# PressureSensorShield.net
KiCad netlist of a schematic drawn in EAGLE
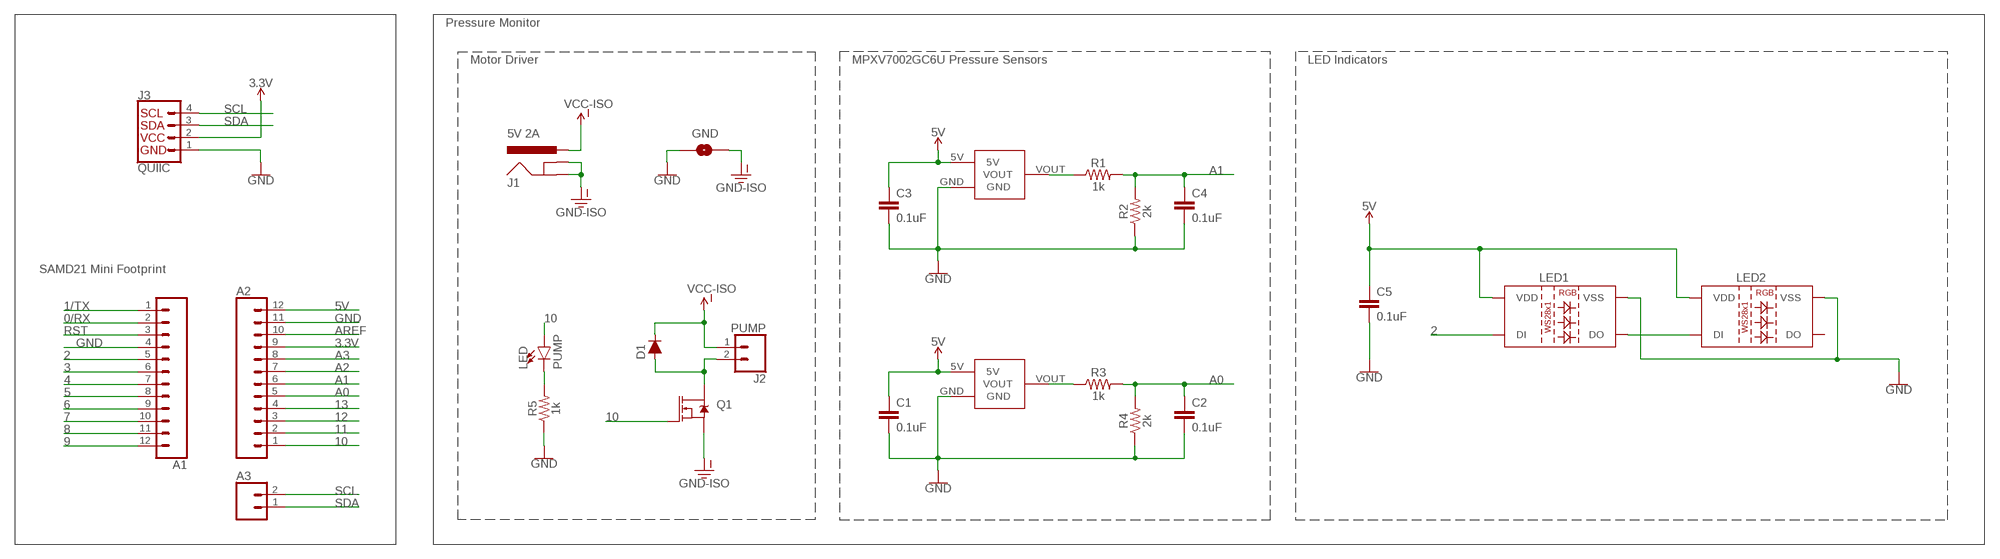
[diagram p0: schematic, sheet 1]

(export (version "E")
  (design (tool "Eeschema 10.0.6"))
  (components
    (comp (ref "A1")
      (value "CONN_12")
      (footprint "eagle-import:1X12")
      (libsource (lib "eagle-import") (part "CONN_12"))
    )
    (comp (ref "A2")
      (value "CONN_12")
      (footprint "eagle-import:1X12")
      (libsource (lib "eagle-import") (part "CONN_12"))
    )
    (comp (ref "A3")
      (value "CONN_02")
      (footprint "eagle-import:1X02")
      (libsource (lib "eagle-import") (part "CONN_02"))
    )
    (comp (ref "C1")
      (value "0.1uF")
      (footprint "eagle-import:CAP-PTH-SMALL-KIT")
      (libsource (lib "eagle-import") (part "0.1UF-KIT-EZ-50V-20%"))
    )
    (comp (ref "C2")
      (value "0.1uF")
      (footprint "eagle-import:CAP-PTH-SMALL-KIT")
      (libsource (lib "eagle-import") (part "0.1UF-KIT-EZ-50V-20%"))
    )
    (comp (ref "C3")
      (value "0.1uF")
      (footprint "eagle-import:CAP-PTH-SMALL-KIT")
      (libsource (lib "eagle-import") (part "0.1UF-KIT-EZ-50V-20%"))
    )
    (comp (ref "C4")
      (value "0.1uF")
      (footprint "eagle-import:CAP-PTH-SMALL-KIT")
      (libsource (lib "eagle-import") (part "0.1UF-KIT-EZ-50V-20%"))
    )
    (comp (ref "C5")
      (value "0.1uF")
      (footprint "eagle-import:CAP-PTH-SMALL-KIT")
      (libsource (lib "eagle-import") (part "0.1UF-KIT-EZ-50V-20%"))
    )
    (comp (ref "D1")
      (value "DIODE-KIT")
      (footprint "eagle-import:DIODE-1N4148-KIT")
      (libsource (lib "eagle-import") (part "DIODE-KIT"))
    )
    (comp (ref "GND")
      (value "JUMPER-SMT_2_NO_NO-SILK")
      (footprint "eagle-import:SMT-JUMPER_2_NO_NO-SILK")
      (libsource (lib "eagle-import") (part "JUMPER-SMT_2_NO_NO-SILK"))
    )
    (comp (ref "J1")
      (value "5V 2A")
      (footprint "eagle-import:POWER_JACK_PTH")
      (libsource (lib "eagle-import") (part "POWER_JACK"))
    )
    (comp (ref "J2")
      (value "PUMP")
      (footprint "eagle-import:SCREWTERMINAL-3.5MM-2")
      (libsource (lib "eagle-import") (part "CONN_023.5MM"))
    )
    (comp (ref "J3")
      (value "QUIIC")
      (footprint "eagle-import:JST04_1MM_RA")
      (libsource (lib "eagle-import") (part "I2C_STANDARDQWIIC"))
    )
    (comp (ref "LED")
      (value "PUMP")
      (footprint "eagle-import:LED_3MM")
      (libsource (lib "eagle-import") (part "LED3MM"))
    )
    (comp (ref "LED1")
      (value "WS2812B")
      (footprint "eagle-import:WS2812B")
      (libsource (lib "eagle-import") (part "WS2812B"))
    )
    (comp (ref "LED2")
      (value "WS2812B")
      (footprint "eagle-import:WS2812B")
      (libsource (lib "eagle-import") (part "WS2812B"))
    )
    (comp (ref "Q1")
      (value "MOSFET-NCH-FQP30N06L")
      (footprint "eagle-import:TO220V")
      (libsource (lib "eagle-import") (part "MOSFET-NCH-FQP30N06L"))
    )
    (comp (ref "R1")
      (value "1k")
      (footprint "eagle-import:AXIAL-0.3-KIT")
      (libsource (lib "eagle-import") (part "1KOHM-HORIZ_KIT-1/4W-1%"))
    )
    (comp (ref "R2")
      (value "2k")
      (footprint "eagle-import:AXIAL-0.3-KIT")
      (libsource (lib "eagle-import") (part "1KOHM-HORIZ_KIT-1/4W-1%"))
    )
    (comp (ref "R3")
      (value "1k")
      (footprint "eagle-import:AXIAL-0.3-KIT")
      (libsource (lib "eagle-import") (part "1KOHM-HORIZ_KIT-1/4W-1%"))
    )
    (comp (ref "R4")
      (value "2k")
      (footprint "eagle-import:AXIAL-0.3-KIT")
      (libsource (lib "eagle-import") (part "1KOHM-HORIZ_KIT-1/4W-1%"))
    )
    (comp (ref "R5")
      (value "1k")
      (footprint "eagle-import:AXIAL-0.3-KIT")
      (libsource (lib "eagle-import") (part "1KOHM-HORIZ_KIT-1/4W-1%"))
    )
    (comp (ref "SENSOR")
      (value "SENSOR 1")
      (footprint "eagle-import:SMALL_OUTLINE")
      (libsource (lib "eagle-import") (part "MPXV7002GC6T1"))
    )
    (comp (ref "SENSOR2")
      (value "SENSOR 2")
      (footprint "eagle-import:SMALL_OUTLINE")
      (libsource (lib "eagle-import") (part "MPXV7002GC6T1"))
    )
  )
  (nets
    (net (code "1") (name "/0{slash}RX") (class "Default")
      (node (ref "A1") (pin "2") (pinfunction "2_2") (pintype "passive"))
    )
    (net (code "2") (name "/1{slash}TX") (class "Default")
      (node (ref "A1") (pin "1") (pinfunction "1_1") (pintype "passive"))
    )
    (net (code "3") (name "/2") (class "Default")
      (node (ref "A1") (pin "5") (pinfunction "5_5") (pintype "passive"))
      (node (ref "LED1") (pin "4") (pinfunction "DI_4") (pintype "bidirectional"))
    )
    (net (code "4") (name "/3") (class "Default")
      (node (ref "A1") (pin "6") (pinfunction "6_6") (pintype "passive"))
    )
    (net (code "5") (name "/4") (class "Default")
      (node (ref "A1") (pin "7") (pinfunction "7_7") (pintype "passive"))
    )
    (net (code "6") (name "/5") (class "Default")
      (node (ref "A1") (pin "8") (pinfunction "8_8") (pintype "passive"))
    )
    (net (code "7") (name "/6") (class "Default")
      (node (ref "A1") (pin "9") (pinfunction "9_9") (pintype "passive"))
    )
    (net (code "8") (name "/7") (class "Default")
      (node (ref "A1") (pin "10") (pinfunction "10_10") (pintype "passive"))
    )
    (net (code "9") (name "/8") (class "Default")
      (node (ref "A1") (pin "11") (pinfunction "11_11") (pintype "passive"))
    )
    (net (code "10") (name "/9") (class "Default")
      (node (ref "A1") (pin "12") (pinfunction "12_12") (pintype "passive"))
    )
    (net (code "11") (name "/10") (class "Default")
      (node (ref "A2") (pin "1") (pinfunction "1_1") (pintype "passive"))
      (node (ref "LED") (pin "A") (pinfunction "A_A") (pintype "passive"))
      (node (ref "Q1") (pin "1") (pinfunction "G_1") (pintype "bidirectional"))
    )
    (net (code "12") (name "/11") (class "Default")
      (node (ref "A2") (pin "2") (pinfunction "2_2") (pintype "passive"))
    )
    (net (code "13") (name "/12") (class "Default")
      (node (ref "A2") (pin "3") (pinfunction "3_3") (pintype "passive"))
    )
    (net (code "14") (name "/13") (class "Default")
      (node (ref "A2") (pin "4") (pinfunction "4_4") (pintype "passive"))
    )
    (net (code "15") (name "/A0") (class "Default")
      (node (ref "A2") (pin "5") (pinfunction "5_5") (pintype "passive"))
      (node (ref "C2") (pin "1") (pinfunction "1_1") (pintype "passive"))
      (node (ref "R3") (pin "P$2") (pinfunction "2_P$2") (pintype "passive"))
      (node (ref "R4") (pin "P$2") (pinfunction "2_P$2") (pintype "passive"))
    )
    (net (code "16") (name "/A1") (class "Default")
      (node (ref "A2") (pin "6") (pinfunction "6_6") (pintype "passive"))
      (node (ref "C4") (pin "1") (pinfunction "1_1") (pintype "passive"))
      (node (ref "R1") (pin "P$2") (pinfunction "2_P$2") (pintype "passive"))
      (node (ref "R2") (pin "P$2") (pinfunction "2_P$2") (pintype "passive"))
    )
    (net (code "17") (name "/A2") (class "Default")
      (node (ref "A2") (pin "7") (pinfunction "7_7") (pintype "passive"))
    )
    (net (code "18") (name "/A3") (class "Default")
      (node (ref "A2") (pin "8") (pinfunction "8_8") (pintype "passive"))
    )
    (net (code "19") (name "/AREF") (class "Default")
      (node (ref "A2") (pin "10") (pinfunction "10_10") (pintype "passive"))
    )
    (net (code "20") (name "/RST") (class "Default")
      (node (ref "A1") (pin "3") (pinfunction "3_3") (pintype "passive"))
    )
    (net (code "21") (name "/SCL") (class "Default")
      (node (ref "A3") (pin "2") (pinfunction "2_2") (pintype "passive"))
      (node (ref "J3") (pin "4") (pinfunction "4_4") (pintype "passive"))
    )
    (net (code "22") (name "/SDA") (class "Default")
      (node (ref "A3") (pin "1") (pinfunction "1_1") (pintype "passive"))
      (node (ref "J3") (pin "3") (pinfunction "3_3") (pintype "passive"))
    )
    (net (code "23") (name "3.3V") (class "Default")
      (node (ref "A2") (pin "9") (pinfunction "9_9") (pintype "passive"))
      (node (ref "J3") (pin "2") (pinfunction "2_2") (pintype "power_in"))
    )
    (net (code "24") (name "5V") (class "Default")
      (node (ref "A2") (pin "12") (pinfunction "12_12") (pintype "passive"))
      (node (ref "C1") (pin "1") (pinfunction "1_1") (pintype "passive"))
      (node (ref "C3") (pin "1") (pinfunction "1_1") (pintype "passive"))
      (node (ref "C5") (pin "1") (pinfunction "1_1") (pintype "passive"))
      (node (ref "LED1") (pin "1") (pinfunction "VDD_1") (pintype "bidirectional"))
      (node (ref "LED2") (pin "1") (pinfunction "VDD_1") (pintype "bidirectional"))
      (node (ref "SENSOR") (pin "5V") (pinfunction "5V_5V") (pintype "power_in"))
      (node (ref "SENSOR2") (pin "5V") (pinfunction "5V_5V") (pintype "power_in"))
    )
    (net (code "25") (name "GND") (class "Default")
      (node (ref "A1") (pin "4") (pinfunction "4_4") (pintype "passive"))
      (node (ref "A2") (pin "11") (pinfunction "11_11") (pintype "passive"))
      (node (ref "C1") (pin "2") (pinfunction "2_2") (pintype "passive"))
      (node (ref "C2") (pin "2") (pinfunction "2_2") (pintype "passive"))
      (node (ref "C3") (pin "2") (pinfunction "2_2") (pintype "passive"))
      (node (ref "C4") (pin "2") (pinfunction "2_2") (pintype "passive"))
      (node (ref "C5") (pin "2") (pinfunction "2_2") (pintype "passive"))
      (node (ref "GND") (pin "1") (pinfunction "1_1") (pintype "passive"))
      (node (ref "J3") (pin "1") (pinfunction "1_1") (pintype "power_in"))
      (node (ref "LED1") (pin "3") (pinfunction "VSS_3") (pintype "bidirectional"))
      (node (ref "LED2") (pin "3") (pinfunction "VSS_3") (pintype "bidirectional"))
      (node (ref "R2") (pin "P$1") (pinfunction "1_P$1") (pintype "passive"))
      (node (ref "R4") (pin "P$1") (pinfunction "1_P$1") (pintype "passive"))
      (node (ref "R5") (pin "P$1") (pinfunction "1_P$1") (pintype "passive"))
      (node (ref "SENSOR") (pin "GND") (pinfunction "GND_GND") (pintype "power_in"))
      (node (ref "SENSOR2") (pin "GND") (pinfunction "GND_GND") (pintype "power_in"))
    )
    (net (code "26") (name "GND-ISO") (class "Default")
      (node (ref "GND") (pin "2") (pinfunction "2_2") (pintype "passive"))
      (node (ref "J1") (pin "GND") (pinfunction "GND_GND") (pintype "bidirectional"))
      (node (ref "J1") (pin "GNDBREAK") (pinfunction "GNDBREAK_GNDBREAK") (pintype "bidirectional"))
      (node (ref "Q1") (pin "3") (pinfunction "S_3") (pintype "bidirectional"))
    )
    (net (code "27") (name "Net-(LED-C)") (class "Default")
      (node (ref "LED") (pin "K") (pinfunction "C_K") (pintype "passive"))
      (node (ref "R5") (pin "P$2") (pinfunction "2_P$2") (pintype "passive"))
    )
    (net (code "28") (name "Net-(LED1-DO)") (class "Default")
      (node (ref "LED1") (pin "2") (pinfunction "DO_2") (pintype "bidirectional"))
      (node (ref "LED2") (pin "4") (pinfunction "DI_4") (pintype "bidirectional"))
    )
    (net (code "29") (name "Net-(Q1-D)") (class "Default")
      (node (ref "D1") (pin "A") (pinfunction "A_A") (pintype "passive"))
      (node (ref "J2") (pin "2") (pinfunction "2_2") (pintype "passive"))
      (node (ref "Q1") (pin "2") (pinfunction "D_2") (pintype "bidirectional"))
    )
    (net (code "30") (name "Net-(R1-1)") (class "Default")
      (node (ref "R1") (pin "P$1") (pinfunction "1_P$1") (pintype "passive"))
      (node (ref "SENSOR2") (pin "VOUT") (pinfunction "VOUT_VOUT") (pintype "output"))
    )
    (net (code "31") (name "Net-(R3-1)") (class "Default")
      (node (ref "R3") (pin "P$1") (pinfunction "1_P$1") (pintype "passive"))
      (node (ref "SENSOR") (pin "VOUT") (pinfunction "VOUT_VOUT") (pintype "output"))
    )
    (net (code "32") (name "VCC-ISO") (class "Default")
      (node (ref "D1") (pin "C") (pinfunction "C_C") (pintype "passive"))
      (node (ref "J1") (pin "PWR") (pinfunction "PWR_PWR") (pintype "bidirectional"))
      (node (ref "J2") (pin "1") (pinfunction "1_1") (pintype "passive"))
    )
    (net (code "33") (name "unconnected-(LED2-DO-Pad2)") (class "Default")
      (node (ref "LED2") (pin "2") (pinfunction "DO_2") (pintype "bidirectional"))
    )
  )
)
